# U-blox_ZED_F9P_GPS_RTK.net
KiCad netlist of a schematic drawn in EasyEDA Pro
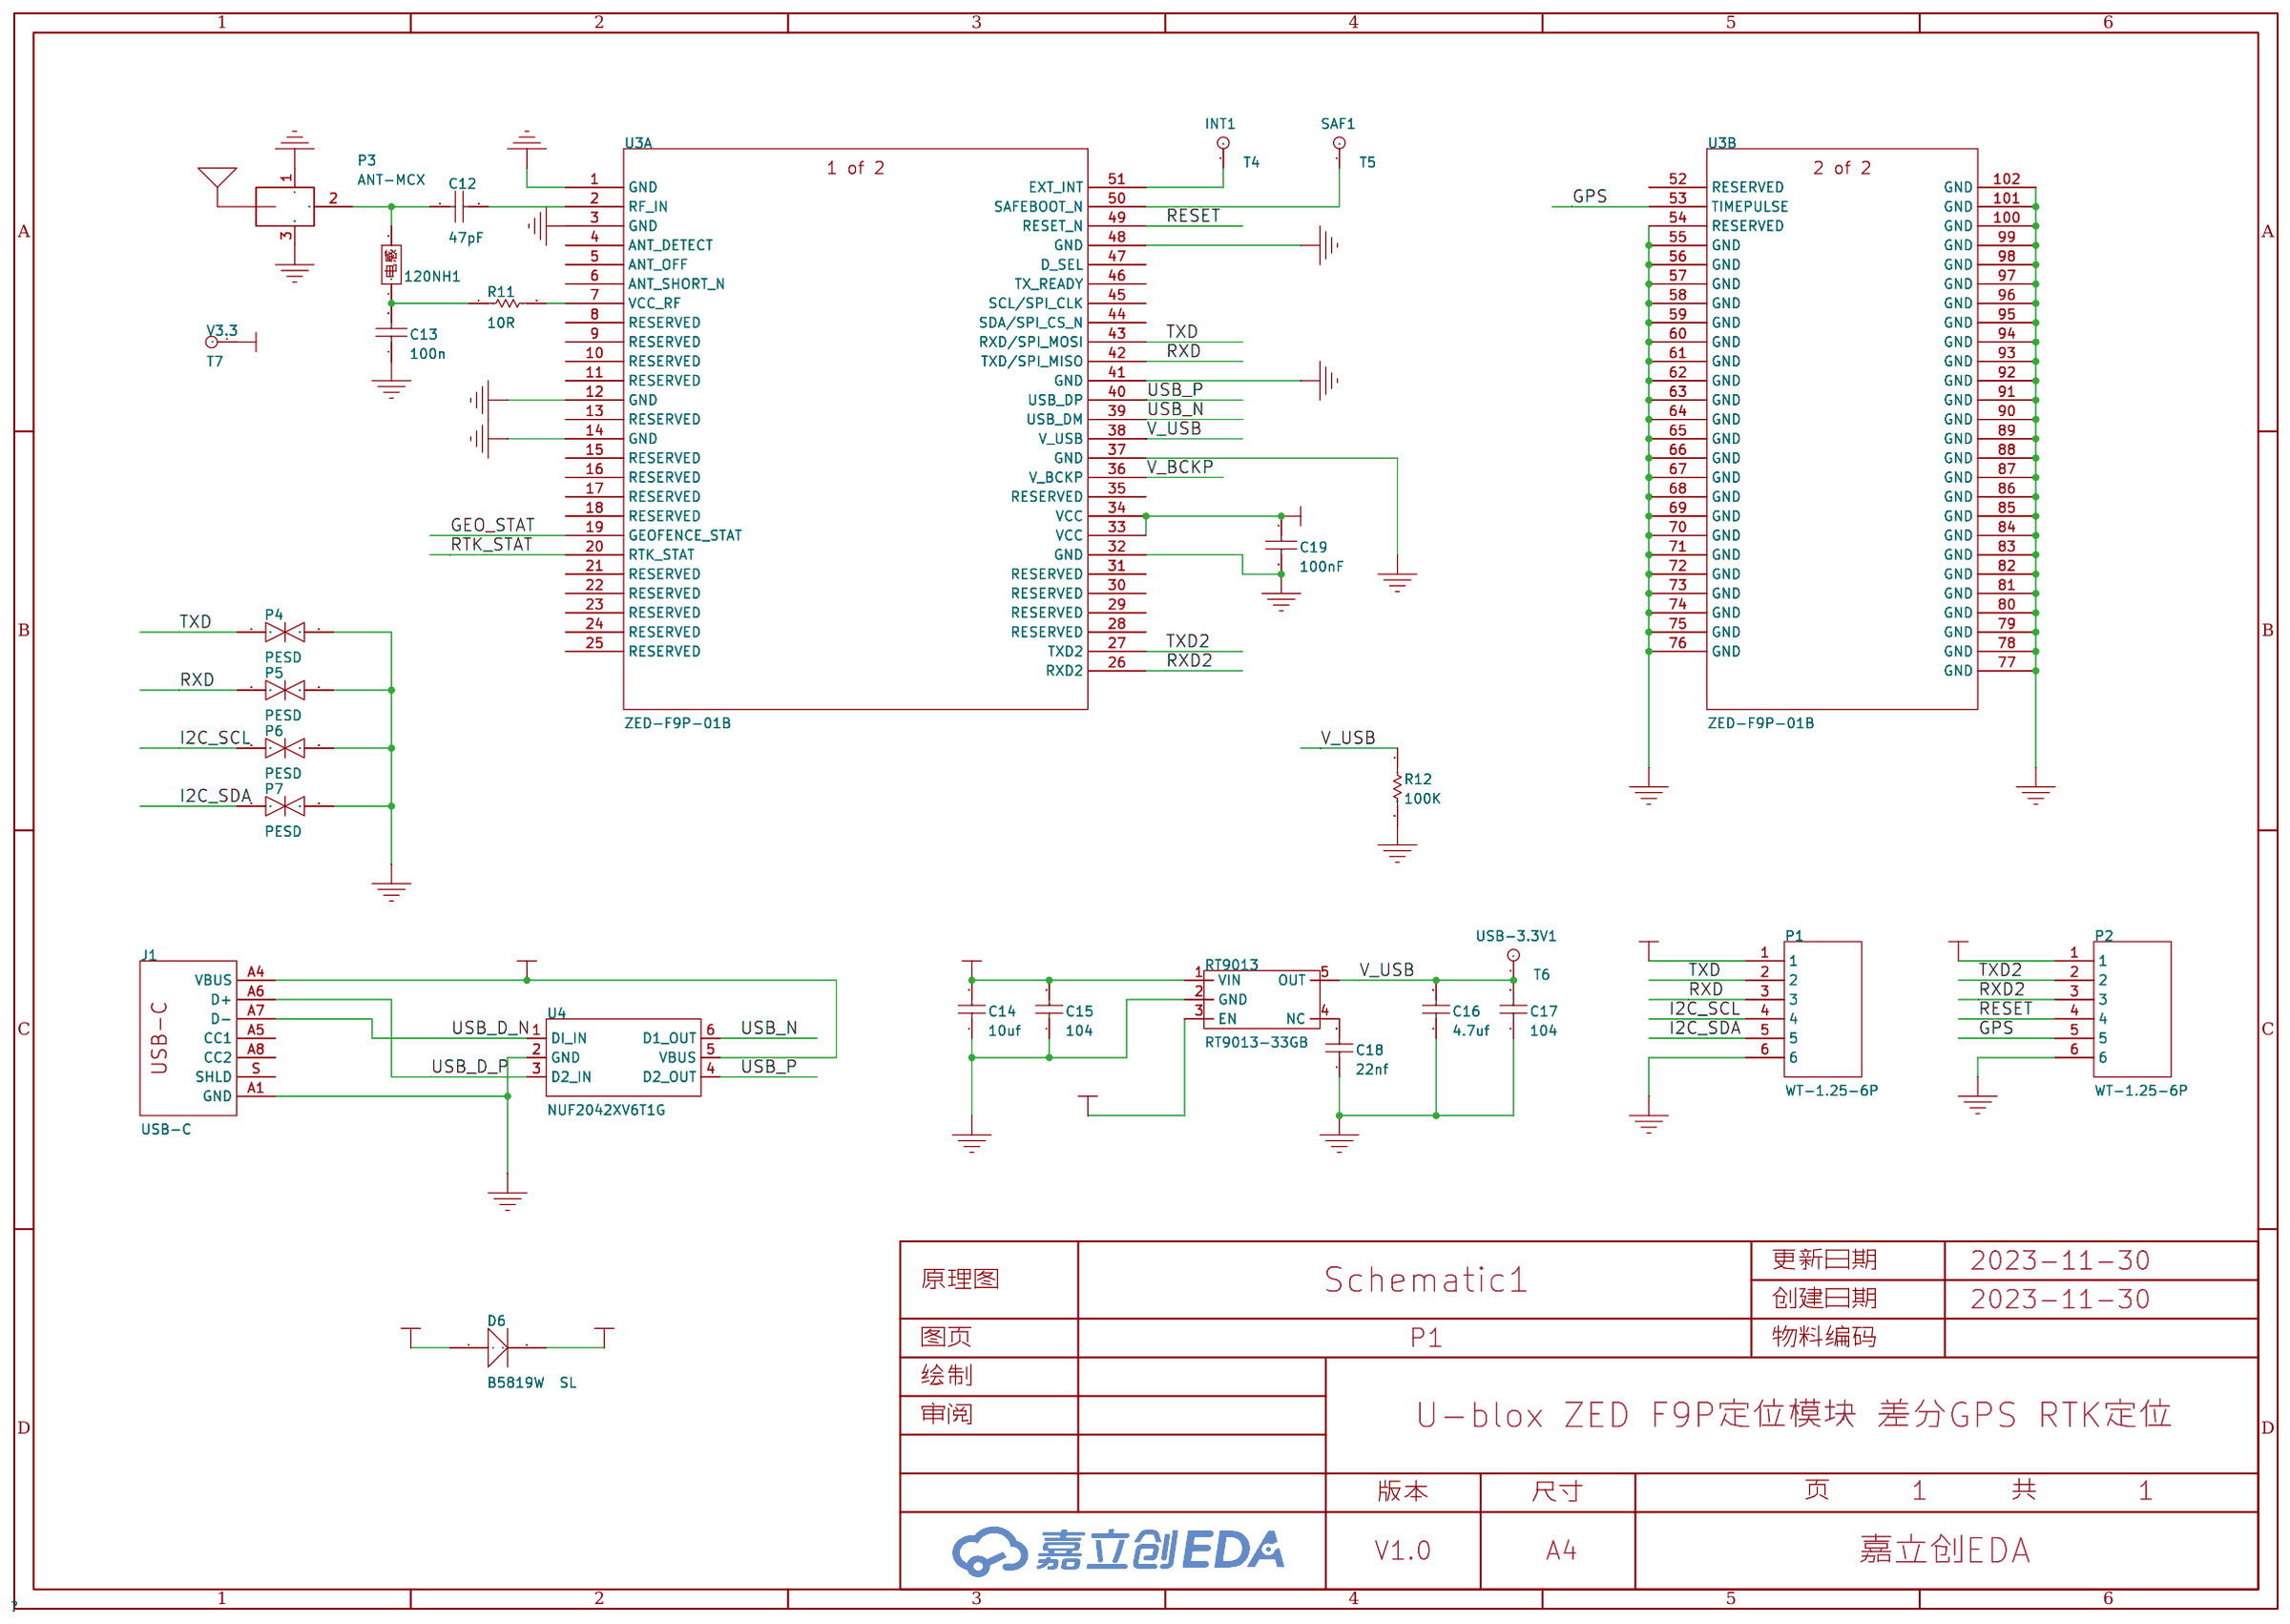
[diagram p0: P1_GPS_F9P]
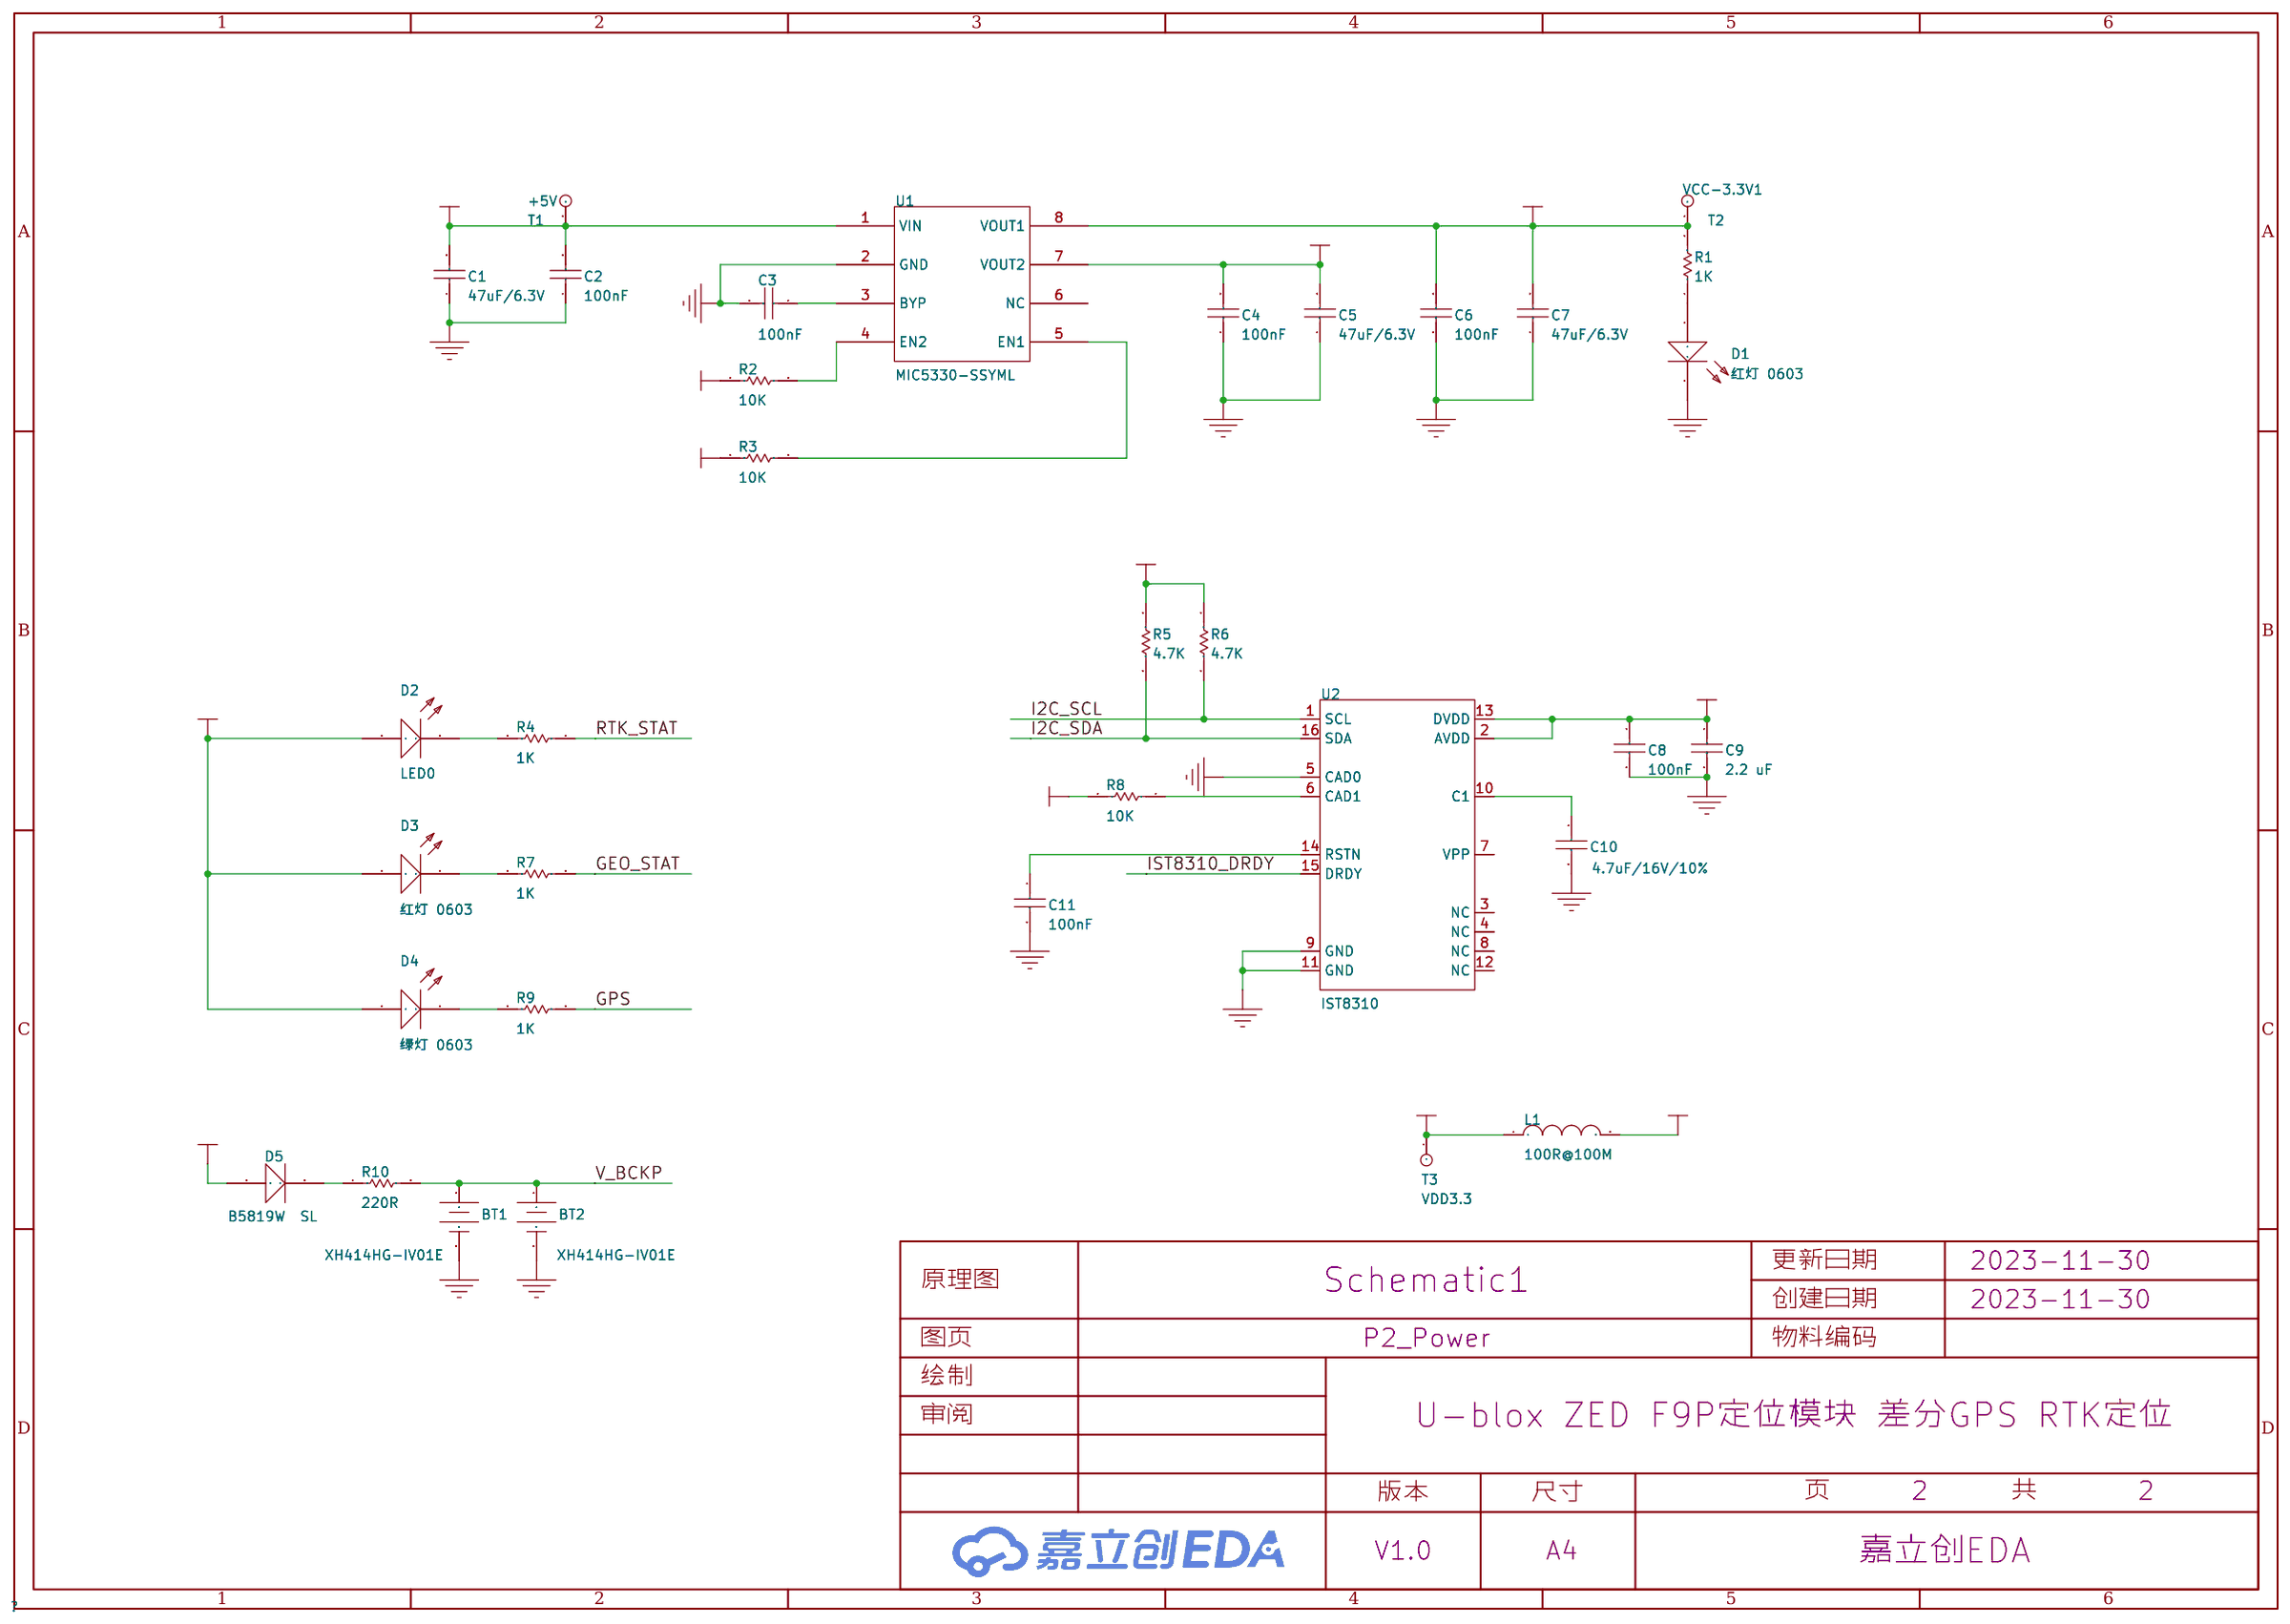
[diagram p1: P2_Power]

(export (version "E")
  (design (tool "Eeschema 10.0.6"))
  (components
    (comp (ref "120NH1") (value "L") (footprint "easyedapro:0402R") (libsource (lib "easyedapro") (part "L")))
    (comp (ref "C12")
      (value "100pF")
      (footprint "easyedapro:0603C")
      (description "Capacitor")
      (fields (field (name "Publisher") "Altium Limited"))
      (libsource (lib "easyedapro") (part "Cap"))
    )
    (comp (ref "C13")
      (value "100pF")
      (footprint "easyedapro:0603C")
      (description "Capacitor")
      (fields (field (name "Publisher") "Altium Limited"))
      (libsource (lib "easyedapro") (part "Cap"))
    )
    (comp (ref "C14")
      (value "10uf")
      (footprint "easyedapro:0603C")
      (description "无极性电容")
      (libsource (lib "easyedapro") (part "CAP"))
    )
    (comp (ref "C15")
      (value "104")
      (footprint "easyedapro:0603C")
      (description "无极性电容")
      (libsource (lib "easyedapro") (part "CAP"))
    )
    (comp (ref "C16")
      (value "4.7uf")
      (footprint "easyedapro:0603C")
      (description "无极性电容")
      (libsource (lib "easyedapro") (part "CAP"))
    )
    (comp (ref "C17")
      (value "104")
      (footprint "easyedapro:0603C")
      (description "无极性电容")
      (libsource (lib "easyedapro") (part "CAP"))
    )
    (comp (ref "C18")
      (value "22nf")
      (footprint "easyedapro:0603C")
      (description "无极性电容")
      (libsource (lib "easyedapro") (part "CAP"))
    )
    (comp (ref "C19")
      (value "100pF")
      (footprint "easyedapro:0603C")
      (description "Capacitor")
      (fields (field (name "Publisher") "Altium Limited"))
      (libsource (lib "easyedapro") (part "Cap"))
    )
    (comp (ref "D6")
      (value "B5819W  SL")
      (footprint "easyedapro:SOD-123")
      (description "肖特基二极管")
      (libsource (lib "easyedapro") (part "SOD-123 B5819W  SL"))
    )
    (comp (ref "INT1") (value "T4") (footprint "easyedapro:TP") (libsource (lib "easyedapro") (part "TP")))
    (comp (ref "J1")
      (value "USB-C")
      (footprint "easyedapro:USB-Type-C")
      (libsource (lib "easyedapro") (part "USB3.1"))
    )
    (comp (ref "P1")
      (value "WT-1.25-6P")
      (footprint "easyedapro:GH-1.25-6P")
      (libsource (lib "easyedapro") (part "GH-1.25-6P"))
    )
    (comp (ref "P2")
      (value "WT-1.25-6P")
      (footprint "easyedapro:GH-1.25-6P")
      (libsource (lib "easyedapro") (part "GH-1.25-6P"))
    )
    (comp (ref "P3")
      (value "ANT-MCX")
      (footprint "easyedapro:ANT-MCX")
      (libsource (lib "easyedapro") (part "ANT"))
    )
    (comp (ref "P4")
      (value "PESD")
      (footprint "easyedapro:PESD0402")
      (description "PESD 0402")
      (libsource (lib "easyedapro") (part "PESD"))
    )
    (comp (ref "P5")
      (value "PESD")
      (footprint "easyedapro:PESD0402")
      (description "PESD 0402")
      (libsource (lib "easyedapro") (part "PESD"))
    )
    (comp (ref "P6")
      (value "PESD")
      (footprint "easyedapro:PESD0402")
      (description "PESD 0402")
      (libsource (lib "easyedapro") (part "PESD"))
    )
    (comp (ref "P7")
      (value "PESD")
      (footprint "easyedapro:PESD0402")
      (description "PESD 0402")
      (libsource (lib "easyedapro") (part "PESD"))
    )
    (comp (ref "R11")
      (value "1K")
      (footprint "easyedapro:0402R")
      (description "Resistor")
      (fields (field (name "Publisher") "Altium Limited"))
      (libsource (lib "easyedapro") (part "Res1"))
    )
    (comp (ref "R12")
      (value "1K")
      (footprint "easyedapro:0402R")
      (description "Resistor")
      (fields (field (name "Publisher") "Altium Limited"))
      (libsource (lib "easyedapro") (part "Res1"))
    )
    (comp (ref "RT9013")
      (value "RT9013-33GB")
      (footprint "easyedapro:SOT23-5L")
      (description "3.3V 500mA LDO")
      (libsource (lib "easyedapro") (part "RT9013"))
    )
    (comp (ref "SAF1") (value "T5") (footprint "easyedapro:TP") (libsource (lib "easyedapro") (part "TP")))
    (comp (ref "U3")
      (value "ZED-F9P-01B")
      (footprint "easyedapro:ZED-F9P-01B_UBL")
      (description "多频 GNSS 接收机")
      (fields
        (field (name "Manufacturer_Part_Number") "ZED-F9R-01B")
        (field (name "Copyright") "Copyright (C) 2022 Ultra Librarian. All rights reserved.")
      )
      (libsource (lib "easyedapro") (part "ZED-F9P-01B"))
    )
    (comp (ref "U4")
      (value "NUF2042XV6T1G")
      (footprint "easyedapro:SOT-563-6")
      (libsource (lib "easyedapro") (part "NUF2042XV6T1G"))
    )
    (comp (ref "USB-3.3V1")
      (value "T6")
      (footprint "easyedapro:TP")
      (libsource (lib "easyedapro") (part "TP"))
    )
    (comp (ref "V3.3") (value "T7") (footprint "easyedapro:TP") (libsource (lib "easyedapro") (part "TP")))
    (comp (ref "BT1")
      (value "XH414HG-IV01E")
      (footprint "easyedapro:XH414HG-IV01E")
      (libsource (lib "easyedapro") (part "Battery"))
    )
    (comp (ref "BT2")
      (value "XH414HG-IV01E")
      (footprint "easyedapro:XH414HG-IV01E")
      (libsource (lib "easyedapro") (part "Battery"))
    )
    (comp (ref "C1")
      (value "100pF")
      (footprint "easyedapro:0603C")
      (description "Capacitor")
      (fields (field (name "Publisher") "Altium Limited"))
      (libsource (lib "easyedapro") (part "Cap"))
    )
    (comp (ref "C2")
      (value "100pF")
      (footprint "easyedapro:0603C")
      (description "Capacitor")
      (fields (field (name "Publisher") "Altium Limited"))
      (libsource (lib "easyedapro") (part "Cap"))
    )
    (comp (ref "C3")
      (value "100pF")
      (footprint "easyedapro:0603C")
      (description "Capacitor")
      (fields (field (name "Publisher") "Altium Limited"))
      (libsource (lib "easyedapro") (part "Cap"))
    )
    (comp (ref "C4")
      (value "100pF")
      (footprint "easyedapro:0603C")
      (description "Capacitor")
      (fields (field (name "Publisher") "Altium Limited"))
      (libsource (lib "easyedapro") (part "Cap"))
    )
    (comp (ref "C5")
      (value "100pF")
      (footprint "easyedapro:0603C")
      (description "Capacitor")
      (fields (field (name "Publisher") "Altium Limited"))
      (libsource (lib "easyedapro") (part "Cap"))
    )
    (comp (ref "C6")
      (value "100pF")
      (footprint "easyedapro:0603C")
      (description "Capacitor")
      (fields (field (name "Publisher") "Altium Limited"))
      (libsource (lib "easyedapro") (part "Cap"))
    )
    (comp (ref "C7")
      (value "100pF")
      (footprint "easyedapro:0603C")
      (description "Capacitor")
      (fields (field (name "Publisher") "Altium Limited"))
      (libsource (lib "easyedapro") (part "Cap"))
    )
    (comp (ref "C8")
      (value "100pF")
      (footprint "easyedapro:0603C")
      (description "Capacitor")
      (fields (field (name "Publisher") "Altium Limited"))
      (libsource (lib "easyedapro") (part "Cap"))
    )
    (comp (ref "C9")
      (value "100pF")
      (footprint "easyedapro:0603C")
      (description "Capacitor")
      (fields (field (name "Publisher") "Altium Limited"))
      (libsource (lib "easyedapro") (part "Cap"))
    )
    (comp (ref "C10")
      (value "100pF")
      (footprint "easyedapro:0603C")
      (description "Capacitor")
      (fields (field (name "Publisher") "Altium Limited"))
      (libsource (lib "easyedapro") (part "Cap"))
    )
    (comp (ref "C11")
      (value "100pF")
      (footprint "easyedapro:0603C")
      (description "Capacitor")
      (fields (field (name "Publisher") "Altium Limited"))
      (libsource (lib "easyedapro") (part "Cap"))
    )
    (comp (ref "D1")
      (value "红灯 0603")
      (footprint "easyedapro:0603_LED_S1")
      (description "发光二极管")
      (libsource (lib "easyedapro") (part "0603 红灯"))
    )
    (comp (ref "D2")
      (value "LED0")
      (footprint "easyedapro:0603D")
      (description "Typical INFRARED GaAs LED")
      (fields (field (name "Publisher") "Altium Limited"))
      (libsource (lib "easyedapro") (part "LED0"))
    )
    (comp (ref "D3")
      (value "红灯 0603")
      (footprint "easyedapro:0603_LED_S1")
      (description "发光二极管")
      (libsource (lib "easyedapro") (part "0603 红灯"))
    )
    (comp (ref "D4")
      (value "绿灯 0603")
      (footprint "easyedapro:0603_LED_S1")
      (description "发光二极管")
      (libsource (lib "easyedapro") (part "0603 绿灯"))
    )
    (comp (ref "D5")
      (value "B5819W  SL")
      (footprint "easyedapro:SOD-123")
      (description "肖特基二极管")
      (libsource (lib "easyedapro") (part "SOD-123 B5819W  SL"))
    )
    (comp (ref "L1")
      (value "10mH")
      (footprint "easyedapro:0603L")
      (description "Inductor")
      (fields (field (name "Publisher") "Altium Limited"))
      (libsource (lib "easyedapro") (part "Inductor"))
    )
    (comp (ref "R1")
      (value "1K")
      (footprint "easyedapro:0402R")
      (description "Resistor")
      (fields (field (name "Publisher") "Altium Limited"))
      (libsource (lib "easyedapro") (part "Res1"))
    )
    (comp (ref "R2")
      (value "1K")
      (footprint "easyedapro:0402R")
      (description "Resistor")
      (fields (field (name "Publisher") "Altium Limited"))
      (libsource (lib "easyedapro") (part "Res1"))
    )
    (comp (ref "R3")
      (value "1K")
      (footprint "easyedapro:0402R")
      (description "Resistor")
      (fields (field (name "Publisher") "Altium Limited"))
      (libsource (lib "easyedapro") (part "Res1"))
    )
    (comp (ref "R4")
      (value "1K")
      (footprint "easyedapro:0402R")
      (description "Resistor")
      (fields (field (name "Publisher") "Altium Limited"))
      (libsource (lib "easyedapro") (part "Res1"))
    )
    (comp (ref "R5")
      (value "1K")
      (footprint "easyedapro:0402R")
      (description "Resistor")
      (fields (field (name "Publisher") "Altium Limited"))
      (libsource (lib "easyedapro") (part "Res1"))
    )
    (comp (ref "R6")
      (value "1K")
      (footprint "easyedapro:0402R")
      (description "Resistor")
      (fields (field (name "Publisher") "Altium Limited"))
      (libsource (lib "easyedapro") (part "Res1"))
    )
    (comp (ref "R7")
      (value "1K")
      (footprint "easyedapro:0402R")
      (description "Resistor")
      (fields (field (name "Publisher") "Altium Limited"))
      (libsource (lib "easyedapro") (part "Res1"))
    )
    (comp (ref "R8")
      (value "1K")
      (footprint "easyedapro:0402R")
      (description "Resistor")
      (fields (field (name "Publisher") "Altium Limited"))
      (libsource (lib "easyedapro") (part "Res1"))
    )
    (comp (ref "R9")
      (value "1K")
      (footprint "easyedapro:0402R")
      (description "Resistor")
      (fields (field (name "Publisher") "Altium Limited"))
      (libsource (lib "easyedapro") (part "Res1"))
    )
    (comp (ref "R10")
      (value "1K")
      (footprint "easyedapro:0402R")
      (description "Resistor")
      (fields (field (name "Publisher") "Altium Limited"))
      (libsource (lib "easyedapro") (part "Res1"))
    )
    (comp (ref "T1") (value "+5V") (footprint "easyedapro:TP") (libsource (lib "easyedapro") (part "TP")))
    (comp (ref "T3") (value "VDD3.3") (footprint "easyedapro:TP") (libsource (lib "easyedapro") (part "TP")))
    (comp (ref "U1")
      (value "MIC5330-SSYML")
      (footprint "easyedapro:MIC5330-SSYML-TR")
      (libsource (lib "easyedapro") (part "MIC5330-SSYML"))
    )
    (comp (ref "U2")
      (value "IST8310")
      (footprint "easyedapro:LGA16-ITS8310")
      (libsource (lib "easyedapro") (part "IST8310"))
    )
    (comp (ref "VCC-3.3V1")
      (value "T2")
      (footprint "easyedapro:TP")
      (libsource (lib "easyedapro") (part "TP"))
    )
  )
  (nets
    (net (code "1") (name "GEO_STAT") (class "Default")
      (node (ref "R7") (pin "2") (pinfunction "2_2") (pintype "unspecified"))
      (node (ref "U3") (pin "19") (pinfunction "GEOFENCE_STAT_19") (pintype "output"))
    )
    (net (code "2") (name "GND") (class "Default")
      (node (ref "BT1") (pin "2") (pinfunction "2_2") (pintype "unspecified"))
      (node (ref "BT2") (pin "2") (pinfunction "2_2") (pintype "unspecified"))
      (node (ref "C1") (pin "1") (pinfunction "1_1") (pintype "unspecified"))
      (node (ref "C10") (pin "2") (pinfunction "2_2") (pintype "unspecified"))
      (node (ref "C11") (pin "2") (pinfunction "2_2") (pintype "unspecified"))
      (node (ref "C13") (pin "1") (pinfunction "1_1") (pintype "unspecified"))
      (node (ref "C14") (pin "1") (pinfunction "1_1") (pintype "unspecified"))
      (node (ref "C15") (pin "1") (pinfunction "1_1") (pintype "unspecified"))
      (node (ref "C16") (pin "1") (pinfunction "1_1") (pintype "unspecified"))
      (node (ref "C17") (pin "1") (pinfunction "1_1") (pintype "unspecified"))
      (node (ref "C18") (pin "1") (pinfunction "1_1") (pintype "unspecified"))
      (node (ref "C19") (pin "2") (pinfunction "2_2") (pintype "unspecified"))
      (node (ref "C2") (pin "1") (pinfunction "1_1") (pintype "unspecified"))
      (node (ref "C3") (pin "2") (pinfunction "2_2") (pintype "unspecified"))
      (node (ref "C4") (pin "1") (pinfunction "1_1") (pintype "unspecified"))
      (node (ref "C5") (pin "1") (pinfunction "1_1") (pintype "unspecified"))
      (node (ref "C6") (pin "1") (pinfunction "1_1") (pintype "unspecified"))
      (node (ref "C7") (pin "1") (pinfunction "1_1") (pintype "unspecified"))
      (node (ref "C8") (pin "2") (pinfunction "2_2") (pintype "unspecified"))
      (node (ref "C9") (pin "2") (pinfunction "2_2") (pintype "unspecified"))
      (node (ref "D1") (pin "K") (pinfunction "K_K") (pintype "unspecified"))
      (node (ref "J1") (pin "A1") (pinfunction "GND_A1") (pintype "unspecified"))
      (node (ref "P1") (pin "6") (pinfunction "6_6") (pintype "unspecified"))
      (node (ref "P2") (pin "6") (pinfunction "6_6") (pintype "unspecified"))
      (node (ref "P3") (pin "1") (pinfunction "1_1") (pintype "unspecified"))
      (node (ref "P3") (pin "3") (pinfunction "3_3") (pintype "unspecified"))
      (node (ref "P4") (pin "2") (pinfunction "2_2") (pintype "unspecified"))
      (node (ref "P5") (pin "2") (pinfunction "2_2") (pintype "unspecified"))
      (node (ref "P6") (pin "2") (pinfunction "2_2") (pintype "unspecified"))
      (node (ref "P7") (pin "2") (pinfunction "2_2") (pintype "unspecified"))
      (node (ref "R12") (pin "2") (pinfunction "2_2") (pintype "unspecified"))
      (node (ref "RT9013") (pin "2") (pinfunction "GND_2") (pintype "unspecified"))
      (node (ref "U1") (pin "2") (pinfunction "GND_2") (pintype "unspecified"))
      (node (ref "U2") (pin "11") (pinfunction "GND_11") (pintype "unspecified"))
      (node (ref "U2") (pin "5") (pinfunction "CAD0_5") (pintype "unspecified"))
      (node (ref "U2") (pin "9") (pinfunction "GND_9") (pintype "unspecified"))
      (node (ref "U3") (pin "1") (pinfunction "GND_1") (pintype "unspecified"))
      (node (ref "U3") (pin "100") (pinfunction "GND_100") (pintype "unspecified"))
      (node (ref "U3") (pin "101") (pinfunction "GND_101") (pintype "unspecified"))
      (node (ref "U3") (pin "102") (pinfunction "GND_102") (pintype "unspecified"))
      (node (ref "U3") (pin "12") (pinfunction "GND_12") (pintype "unspecified"))
      (node (ref "U3") (pin "14") (pinfunction "GND_14") (pintype "unspecified"))
      (node (ref "U3") (pin "3") (pinfunction "GND_3") (pintype "unspecified"))
      (node (ref "U3") (pin "32") (pinfunction "GND_32") (pintype "unspecified"))
      (node (ref "U3") (pin "37") (pinfunction "GND_37") (pintype "unspecified"))
      (node (ref "U3") (pin "41") (pinfunction "GND_41") (pintype "unspecified"))
      (node (ref "U3") (pin "48") (pinfunction "GND_48") (pintype "unspecified"))
      (node (ref "U3") (pin "54") (pinfunction "RESERVED_54") (pintype "unspecified"))
      (node (ref "U3") (pin "55") (pinfunction "GND_55") (pintype "unspecified"))
      (node (ref "U3") (pin "56") (pinfunction "GND_56") (pintype "unspecified"))
      (node (ref "U3") (pin "57") (pinfunction "GND_57") (pintype "unspecified"))
      (node (ref "U3") (pin "58") (pinfunction "GND_58") (pintype "unspecified"))
      (node (ref "U3") (pin "59") (pinfunction "GND_59") (pintype "unspecified"))
      (node (ref "U3") (pin "60") (pinfunction "GND_60") (pintype "unspecified"))
      (node (ref "U3") (pin "61") (pinfunction "GND_61") (pintype "unspecified"))
      (node (ref "U3") (pin "62") (pinfunction "GND_62") (pintype "unspecified"))
      (node (ref "U3") (pin "63") (pinfunction "GND_63") (pintype "unspecified"))
      (node (ref "U3") (pin "64") (pinfunction "GND_64") (pintype "unspecified"))
      (node (ref "U3") (pin "65") (pinfunction "GND_65") (pintype "unspecified"))
      (node (ref "U3") (pin "66") (pinfunction "GND_66") (pintype "unspecified"))
      (node (ref "U3") (pin "67") (pinfunction "GND_67") (pintype "unspecified"))
      (node (ref "U3") (pin "68") (pinfunction "GND_68") (pintype "unspecified"))
      (node (ref "U3") (pin "69") (pinfunction "GND_69") (pintype "unspecified"))
      (node (ref "U3") (pin "70") (pinfunction "GND_70") (pintype "unspecified"))
      (node (ref "U3") (pin "71") (pinfunction "GND_71") (pintype "unspecified"))
      (node (ref "U3") (pin "72") (pinfunction "GND_72") (pintype "unspecified"))
      (node (ref "U3") (pin "73") (pinfunction "GND_73") (pintype "unspecified"))
      (node (ref "U3") (pin "74") (pinfunction "GND_74") (pintype "unspecified"))
      (node (ref "U3") (pin "75") (pinfunction "GND_75") (pintype "unspecified"))
      (node (ref "U3") (pin "76") (pinfunction "GND_76") (pintype "unspecified"))
      (node (ref "U3") (pin "77") (pinfunction "GND_77") (pintype "unspecified"))
      (node (ref "U3") (pin "78") (pinfunction "GND_78") (pintype "unspecified"))
      (node (ref "U3") (pin "79") (pinfunction "GND_79") (pintype "unspecified"))
      (node (ref "U3") (pin "80") (pinfunction "GND_80") (pintype "unspecified"))
      (node (ref "U3") (pin "81") (pinfunction "GND_81") (pintype "unspecified"))
      (node (ref "U3") (pin "82") (pinfunction "GND_82") (pintype "unspecified"))
      (node (ref "U3") (pin "83") (pinfunction "GND_83") (pintype "unspecified"))
      (node (ref "U3") (pin "84") (pinfunction "GND_84") (pintype "unspecified"))
      (node (ref "U3") (pin "85") (pinfunction "GND_85") (pintype "unspecified"))
      (node (ref "U3") (pin "86") (pinfunction "GND_86") (pintype "unspecified"))
      (node (ref "U3") (pin "87") (pinfunction "GND_87") (pintype "unspecified"))
      (node (ref "U3") (pin "88") (pinfunction "GND_88") (pintype "unspecified"))
      (node (ref "U3") (pin "89") (pinfunction "GND_89") (pintype "unspecified"))
      (node (ref "U3") (pin "90") (pinfunction "GND_90") (pintype "unspecified"))
      (node (ref "U3") (pin "91") (pinfunction "GND_91") (pintype "unspecified"))
      (node (ref "U3") (pin "92") (pinfunction "GND_92") (pintype "unspecified"))
      (node (ref "U3") (pin "93") (pinfunction "GND_93") (pintype "unspecified"))
      (node (ref "U3") (pin "94") (pinfunction "GND_94") (pintype "unspecified"))
      (node (ref "U3") (pin "95") (pinfunction "GND_95") (pintype "unspecified"))
      (node (ref "U3") (pin "96") (pinfunction "GND_96") (pintype "unspecified"))
      (node (ref "U3") (pin "97") (pinfunction "GND_97") (pintype "unspecified"))
      (node (ref "U3") (pin "98") (pinfunction "GND_98") (pintype "unspecified"))
      (node (ref "U3") (pin "99") (pinfunction "GND_99") (pintype "unspecified"))
      (node (ref "U4") (pin "2") (pinfunction "GND_2") (pintype "unspecified"))
    )
    (net (code "3") (name "GPS") (class "Default")
      (node (ref "P2") (pin "5") (pinfunction "5_5") (pintype "unspecified"))
      (node (ref "R9") (pin "2") (pinfunction "2_2") (pintype "unspecified"))
      (node (ref "U3") (pin "53") (pinfunction "TIMEPULSE_53") (pintype "output"))
    )
    (net (code "4") (name "I2C_SCL") (class "Default")
      (node (ref "P1") (pin "4") (pinfunction "4_4") (pintype "unspecified"))
      (node (ref "P6") (pin "1") (pinfunction "1_1") (pintype "unspecified"))
      (node (ref "R6") (pin "2") (pinfunction "2_2") (pintype "unspecified"))
      (node (ref "U2") (pin "1") (pinfunction "SCL_1") (pintype "unspecified"))
    )
    (net (code "5") (name "I2C_SDA") (class "Default")
      (node (ref "P1") (pin "5") (pinfunction "5_5") (pintype "unspecified"))
      (node (ref "P7") (pin "1") (pinfunction "1_1") (pintype "unspecified"))
      (node (ref "R5") (pin "2") (pinfunction "2_2") (pintype "unspecified"))
      (node (ref "U2") (pin "16") (pinfunction "SDA_16") (pintype "unspecified"))
    )
    (net (code "6") (name "IST8310_DRDY") (class "Default")
      (node (ref "U2") (pin "15") (pinfunction "DRDY_15") (pintype "unspecified"))
    )
    (net (code "7") (name "Net-(120NH1-Pad1)") (class "Default")
      (node (ref "120NH1") (pin "1") (pinfunction "1_1") (pintype "unspecified"))
      (node (ref "C13") (pin "2") (pinfunction "2_2") (pintype "unspecified"))
      (node (ref "R11") (pin "1") (pinfunction "1_1") (pintype "unspecified"))
    )
    (net (code "8") (name "Net-(120NH1-Pad2)") (class "Default")
      (node (ref "120NH1") (pin "2") (pinfunction "2_2") (pintype "unspecified"))
      (node (ref "C12") (pin "1") (pinfunction "1_1") (pintype "unspecified"))
      (node (ref "P3") (pin "2") (pinfunction "2_2") (pintype "unspecified"))
    )
    (net (code "9") (name "Net-(D1-PadA)") (class "Default")
      (node (ref "D1") (pin "A") (pinfunction "A_A") (pintype "unspecified"))
      (node (ref "R1") (pin "1") (pinfunction "1_1") (pintype "unspecified"))
    )
    (net (code "10") (name "Net-(D2-K)") (class "Default")
      (node (ref "D2") (pin "2") (pinfunction "K_2") (pintype "unspecified"))
      (node (ref "R4") (pin "2") (pinfunction "2_2") (pintype "unspecified"))
    )
    (net (code "11") (name "Net-(D3-PadK)") (class "Default")
      (node (ref "D3") (pin "K") (pinfunction "K_K") (pintype "unspecified"))
      (node (ref "R7") (pin "1") (pinfunction "1_1") (pintype "unspecified"))
    )
    (net (code "12") (name "Net-(D4-PadK)") (class "Default")
      (node (ref "D4") (pin "K") (pinfunction "K_K") (pintype "unspecified"))
      (node (ref "R9") (pin "1") (pinfunction "1_1") (pintype "unspecified"))
    )
    (net (code "13") (name "Net-(D5-K)") (class "Default")
      (node (ref "D5") (pin "2") (pinfunction "K_2") (pintype "unspecified"))
      (node (ref "R10") (pin "1") (pinfunction "1_1") (pintype "unspecified"))
    )
    (net (code "14") (name "Net-(RT9013-NC)") (class "Default")
      (node (ref "C18") (pin "2") (pinfunction "2_2") (pintype "unspecified"))
      (node (ref "RT9013") (pin "4") (pinfunction "NC_4") (pintype "unspecified"))
    )
    (net (code "15") (name "Net-(U1-BYP)") (class "Default")
      (node (ref "C3") (pin "1") (pinfunction "1_1") (pintype "unspecified"))
      (node (ref "U1") (pin "3") (pinfunction "BYP_3") (pintype "unspecified"))
    )
    (net (code "16") (name "Net-(U1-EN1)") (class "Default")
      (node (ref "R3") (pin "2") (pinfunction "2_2") (pintype "unspecified"))
      (node (ref "U1") (pin "5") (pinfunction "EN1_5") (pintype "unspecified"))
    )
    (net (code "17") (name "Net-(U1-EN2)") (class "Default")
      (node (ref "R2") (pin "2") (pinfunction "2_2") (pintype "unspecified"))
      (node (ref "U1") (pin "4") (pinfunction "EN2_4") (pintype "unspecified"))
    )
    (net (code "18") (name "Net-(U2-C1)") (class "Default")
      (node (ref "C10") (pin "1") (pinfunction "1_1") (pintype "unspecified"))
      (node (ref "U2") (pin "10") (pinfunction "C1_10") (pintype "unspecified"))
    )
    (net (code "19") (name "Net-(U2-CAD1)") (class "Default")
      (node (ref "R8") (pin "1") (pinfunction "1_1") (pintype "unspecified"))
      (node (ref "U2") (pin "6") (pinfunction "CAD1_6") (pintype "unspecified"))
    )
    (net (code "20") (name "Net-(U2-RSTN)") (class "Default")
      (node (ref "C11") (pin "1") (pinfunction "1_1") (pintype "unspecified"))
      (node (ref "U2") (pin "14") (pinfunction "RSTN_14") (pintype "unspecified"))
    )
    (net (code "21") (name "Net-(U3A-EXT_INT)") (class "Default")
      (node (ref "INT1") (pin "1") (pinfunction "1_1") (pintype "unspecified"))
      (node (ref "U3") (pin "51") (pinfunction "EXT_INT_51") (pintype "input"))
    )
    (net (code "22") (name "Net-(U3A-RF_IN)") (class "Default")
      (node (ref "C12") (pin "2") (pinfunction "2_2") (pintype "unspecified"))
      (node (ref "U3") (pin "2") (pinfunction "RF_IN_2") (pintype "input"))
    )
    (net (code "23") (name "Net-(U3A-SAFEBOOT_N)") (class "Default")
      (node (ref "SAF1") (pin "1") (pinfunction "1_1") (pintype "unspecified"))
      (node (ref "U3") (pin "50") (pinfunction "SAFEBOOT_N_50") (pintype "input"))
    )
    (net (code "24") (name "Net-(U3A-VCC_RF)") (class "Default")
      (node (ref "R11") (pin "2") (pinfunction "2_2") (pintype "unspecified"))
      (node (ref "U3") (pin "7") (pinfunction "VCC_RF_7") (pintype "unspecified"))
    )
    (net (code "25") (name "RESET") (class "Default")
      (node (ref "P2") (pin "4") (pinfunction "4_4") (pintype "unspecified"))
      (node (ref "U3") (pin "49") (pinfunction "RESET_N_49") (pintype "input"))
    )
    (net (code "26") (name "RTK_STAT") (class "Default")
      (node (ref "R4") (pin "1") (pinfunction "1_1") (pintype "unspecified"))
      (node (ref "U3") (pin "20") (pinfunction "RTK_STAT_20") (pintype "output"))
    )
    (net (code "27") (name "RXD") (class "Default")
      (node (ref "P1") (pin "3") (pinfunction "3_3") (pintype "unspecified"))
      (node (ref "P5") (pin "1") (pinfunction "1_1") (pintype "unspecified"))
      (node (ref "U3") (pin "42") (pinfunction "TXD/SPI_MISO_42") (pintype "output"))
    )
    (net (code "28") (name "RXD2") (class "Default")
      (node (ref "P2") (pin "3") (pinfunction "3_3") (pintype "unspecified"))
      (node (ref "U3") (pin "26") (pinfunction "RXD2_26") (pintype "input"))
    )
    (net (code "29") (name "SEN_3V3") (class "Default")
      (node (ref "C8") (pin "1") (pinfunction "1_1") (pintype "unspecified"))
      (node (ref "C9") (pin "1") (pinfunction "1_1") (pintype "unspecified"))
      (node (ref "L1") (pin "2") (pinfunction "2_2") (pintype "unspecified"))
      (node (ref "R5") (pin "1") (pinfunction "1_1") (pintype "unspecified"))
      (node (ref "R6") (pin "1") (pinfunction "1_1") (pintype "unspecified"))
      (node (ref "R8") (pin "2") (pinfunction "2_2") (pintype "unspecified"))
      (node (ref "U2") (pin "13") (pinfunction "DVDD_13") (pintype "unspecified"))
      (node (ref "U2") (pin "2") (pinfunction "AVDD_2") (pintype "unspecified"))
    )
    (net (code "30") (name "TXD") (class "Default")
      (node (ref "P1") (pin "2") (pinfunction "2_2") (pintype "unspecified"))
      (node (ref "P4") (pin "1") (pinfunction "1_1") (pintype "unspecified"))
      (node (ref "U3") (pin "43") (pinfunction "RXD/SPI_MOSI_43") (pintype "input"))
    )
    (net (code "31") (name "TXD2") (class "Default")
      (node (ref "P2") (pin "2") (pinfunction "2_2") (pintype "unspecified"))
      (node (ref "U3") (pin "27") (pinfunction "TXD2_27") (pintype "output"))
    )
    (net (code "32") (name "USB_D_N") (class "Default")
      (node (ref "J1") (pin "A7") (pinfunction "D-_A7") (pintype "unspecified"))
      (node (ref "U4") (pin "1") (pinfunction "DI_IN_1") (pintype "unspecified"))
    )
    (net (code "33") (name "USB_D_P") (class "Default")
      (node (ref "J1") (pin "A6") (pinfunction "D+_A6") (pintype "unspecified"))
      (node (ref "U4") (pin "3") (pinfunction "D2_IN_3") (pintype "unspecified"))
    )
    (net (code "34") (name "USB_N") (class "Default")
      (node (ref "U3") (pin "39") (pinfunction "USB_DM_39") (pintype "bidirectional"))
      (node (ref "U4") (pin "6") (pinfunction "D1_OUT_6") (pintype "unspecified"))
    )
    (net (code "35") (name "USB_P") (class "Default")
      (node (ref "U3") (pin "40") (pinfunction "USB_DP_40") (pintype "bidirectional"))
      (node (ref "U4") (pin "4") (pinfunction "D2_OUT_4") (pintype "unspecified"))
    )
    (net (code "36") (name "VBUS") (class "Default")
      (node (ref "C14") (pin "2") (pinfunction "2_2") (pintype "unspecified"))
      (node (ref "C15") (pin "2") (pinfunction "2_2") (pintype "unspecified"))
      (node (ref "D6") (pin "1") (pinfunction "A_1") (pintype "unspecified"))
      (node (ref "J1") (pin "A4") (pinfunction "VBUS_A4") (pintype "unspecified"))
      (node (ref "RT9013") (pin "1") (pinfunction "VIN_1") (pintype "unspecified"))
      (node (ref "U4") (pin "5") (pinfunction "VBUS_5") (pintype "unspecified"))
    )
    (net (code "37") (name "VCC_3V3") (class "Default")
      (node (ref "C19") (pin "1") (pinfunction "1_1") (pintype "unspecified"))
      (node (ref "C6") (pin "2") (pinfunction "2_2") (pintype "unspecified"))
      (node (ref "C7") (pin "2") (pinfunction "2_2") (pintype "unspecified"))
      (node (ref "D2") (pin "1") (pinfunction "A_1") (pintype "unspecified"))
      (node (ref "D3") (pin "A") (pinfunction "A_A") (pintype "unspecified"))
      (node (ref "D4") (pin "A") (pinfunction "A_A") (pintype "unspecified"))
      (node (ref "R1") (pin "2") (pinfunction "2_2") (pintype "unspecified"))
      (node (ref "R2") (pin "1") (pinfunction "1_1") (pintype "unspecified"))
      (node (ref "RT9013") (pin "3") (pinfunction "EN_3") (pintype "unspecified"))
      (node (ref "U1") (pin "8") (pinfunction "VOUT1_8") (pintype "unspecified"))
      (node (ref "U3") (pin "33") (pinfunction "VCC_33") (pintype "unspecified"))
      (node (ref "U3") (pin "34") (pinfunction "VCC_34") (pintype "unspecified"))
      (node (ref "V3.3") (pin "1") (pinfunction "1_1") (pintype "unspecified"))
      (node (ref "VCC-3.3V1") (pin "1") (pinfunction "1_1") (pintype "unspecified"))
    )
    (net (code "38") (name "VDD_3V3") (class "Default")
      (node (ref "C4") (pin "2") (pinfunction "2_2") (pintype "unspecified"))
      (node (ref "C5") (pin "2") (pinfunction "2_2") (pintype "unspecified"))
      (node (ref "D5") (pin "1") (pinfunction "A_1") (pintype "unspecified"))
      (node (ref "L1") (pin "1") (pinfunction "1_1") (pintype "unspecified"))
      (node (ref "T3") (pin "1") (pinfunction "1_1") (pintype "unspecified"))
      (node (ref "U1") (pin "7") (pinfunction "VOUT2_7") (pintype "unspecified"))
    )
    (net (code "39") (name "VDD_5V_IN") (class "Default")
      (node (ref "C1") (pin "2") (pinfunction "2_2") (pintype "unspecified"))
      (node (ref "C2") (pin "2") (pinfunction "2_2") (pintype "unspecified"))
      (node (ref "D6") (pin "2") (pinfunction "K_2") (pintype "unspecified"))
      (node (ref "P1") (pin "1") (pinfunction "1_1") (pintype "unspecified"))
      (node (ref "P2") (pin "1") (pinfunction "1_1") (pintype "unspecified"))
      (node (ref "R3") (pin "1") (pinfunction "1_1") (pintype "unspecified"))
      (node (ref "T1") (pin "1") (pinfunction "1_1") (pintype "unspecified"))
      (node (ref "U1") (pin "1") (pinfunction "VIN_1") (pintype "unspecified"))
    )
    (net (code "40") (name "V_BCKP") (class "Default")
      (node (ref "BT1") (pin "1") (pinfunction "1_1") (pintype "unspecified"))
      (node (ref "BT2") (pin "1") (pinfunction "1_1") (pintype "unspecified"))
      (node (ref "R10") (pin "2") (pinfunction "2_2") (pintype "unspecified"))
      (node (ref "U3") (pin "36") (pinfunction "V_BCKP_36") (pintype "unspecified"))
    )
    (net (code "41") (name "V_USB") (class "Default")
      (node (ref "C16") (pin "2") (pinfunction "2_2") (pintype "unspecified"))
      (node (ref "C17") (pin "2") (pinfunction "2_2") (pintype "unspecified"))
      (node (ref "R12") (pin "1") (pinfunction "1_1") (pintype "unspecified"))
      (node (ref "RT9013") (pin "5") (pinfunction "OUT_5") (pintype "unspecified"))
      (node (ref "U3") (pin "38") (pinfunction "V_USB_38") (pintype "unspecified"))
      (node (ref "USB-3.3V1") (pin "1") (pinfunction "1_1") (pintype "unspecified"))
    )
    (net (code "42") (name "unconnected-(J1-CC1-PadA5)") (class "Default")
      (node (ref "J1") (pin "A5") (pinfunction "CC1_A5") (pintype "unspecified"))
    )
    (net (code "43") (name "unconnected-(J1-CC2-PadA8)") (class "Default")
      (node (ref "J1") (pin "A8") (pinfunction "CC2_A8") (pintype "unspecified"))
    )
    (net (code "44") (name "unconnected-(J1-SHLD-PadS)") (class "Default")
      (node (ref "J1") (pin "S") (pinfunction "SHLD_S") (pintype "unspecified"))
    )
    (net (code "45") (name "unconnected-(U1-NC-Pad6)") (class "Default")
      (node (ref "U1") (pin "6") (pinfunction "NC_6") (pintype "unspecified"))
    )
    (net (code "46") (name "unconnected-(U2-NC-Pad3)") (class "Default")
      (node (ref "U2") (pin "3") (pinfunction "NC_3") (pintype "unspecified"))
    )
    (net (code "47") (name "unconnected-(U2-NC-Pad4)") (class "Default")
      (node (ref "U2") (pin "4") (pinfunction "NC_4") (pintype "unspecified"))
    )
    (net (code "48") (name "unconnected-(U2-NC-Pad8)") (class "Default")
      (node (ref "U2") (pin "8") (pinfunction "NC_8") (pintype "unspecified"))
    )
    (net (code "49") (name "unconnected-(U2-NC-Pad12)") (class "Default")
      (node (ref "U2") (pin "12") (pinfunction "NC_12") (pintype "unspecified"))
    )
    (net (code "50") (name "unconnected-(U2-VPP-Pad7)") (class "Default")
      (node (ref "U2") (pin "7") (pinfunction "VPP_7") (pintype "unspecified"))
    )
    (net (code "51") (name "unconnected-(U3A-ANT_DETECT-Pad4)") (class "Default")
      (node (ref "U3") (pin "4") (pinfunction "ANT_DETECT_4") (pintype "input"))
    )
    (net (code "52") (name "unconnected-(U3A-ANT_OFF-Pad5)") (class "Default")
      (node (ref "U3") (pin "5") (pinfunction "ANT_OFF_5") (pintype "output"))
    )
    (net (code "53") (name "unconnected-(U3A-ANT_SHORT_N-Pad6)") (class "Default")
      (node (ref "U3") (pin "6") (pinfunction "ANT_SHORT_N_6") (pintype "input"))
    )
    (net (code "54") (name "unconnected-(U3A-D_SEL-Pad47)") (class "Default")
      (node (ref "U3") (pin "47") (pinfunction "D_SEL_47") (pintype "input"))
    )
    (net (code "55") (name "unconnected-(U3A-RESERVED-Pad8)") (class "Default")
      (node (ref "U3") (pin "8") (pinfunction "RESERVED_8") (pintype "unspecified"))
    )
    (net (code "56") (name "unconnected-(U3A-RESERVED-Pad9)") (class "Default")
      (node (ref "U3") (pin "9") (pinfunction "RESERVED_9") (pintype "unspecified"))
    )
    (net (code "57") (name "unconnected-(U3A-RESERVED-Pad10)") (class "Default")
      (node (ref "U3") (pin "10") (pinfunction "RESERVED_10") (pintype "unspecified"))
    )
    (net (code "58") (name "unconnected-(U3A-RESERVED-Pad11)") (class "Default")
      (node (ref "U3") (pin "11") (pinfunction "RESERVED_11") (pintype "unspecified"))
    )
    (net (code "59") (name "unconnected-(U3A-RESERVED-Pad13)") (class "Default")
      (node (ref "U3") (pin "13") (pinfunction "RESERVED_13") (pintype "unspecified"))
    )
    (net (code "60") (name "unconnected-(U3A-RESERVED-Pad15)") (class "Default")
      (node (ref "U3") (pin "15") (pinfunction "RESERVED_15") (pintype "unspecified"))
    )
    (net (code "61") (name "unconnected-(U3A-RESERVED-Pad16)") (class "Default")
      (node (ref "U3") (pin "16") (pinfunction "RESERVED_16") (pintype "unspecified"))
    )
    (net (code "62") (name "unconnected-(U3A-RESERVED-Pad17)") (class "Default")
      (node (ref "U3") (pin "17") (pinfunction "RESERVED_17") (pintype "unspecified"))
    )
    (net (code "63") (name "unconnected-(U3A-RESERVED-Pad18)") (class "Default")
      (node (ref "U3") (pin "18") (pinfunction "RESERVED_18") (pintype "unspecified"))
    )
    (net (code "64") (name "unconnected-(U3A-RESERVED-Pad21)") (class "Default")
      (node (ref "U3") (pin "21") (pinfunction "RESERVED_21") (pintype "unspecified"))
    )
    (net (code "65") (name "unconnected-(U3A-RESERVED-Pad22)") (class "Default")
      (node (ref "U3") (pin "22") (pinfunction "RESERVED_22") (pintype "unspecified"))
    )
    (net (code "66") (name "unconnected-(U3A-RESERVED-Pad23)") (class "Default")
      (node (ref "U3") (pin "23") (pinfunction "RESERVED_23") (pintype "unspecified"))
    )
    (net (code "67") (name "unconnected-(U3A-RESERVED-Pad24)") (class "Default")
      (node (ref "U3") (pin "24") (pinfunction "RESERVED_24") (pintype "unspecified"))
    )
    (net (code "68") (name "unconnected-(U3A-RESERVED-Pad25)") (class "Default")
      (node (ref "U3") (pin "25") (pinfunction "RESERVED_25") (pintype "unspecified"))
    )
    (net (code "69") (name "unconnected-(U3A-RESERVED-Pad28)") (class "Default")
      (node (ref "U3") (pin "28") (pinfunction "RESERVED_28") (pintype "unspecified"))
    )
    (net (code "70") (name "unconnected-(U3A-RESERVED-Pad29)") (class "Default")
      (node (ref "U3") (pin "29") (pinfunction "RESERVED_29") (pintype "unspecified"))
    )
    (net (code "71") (name "unconnected-(U3A-RESERVED-Pad30)") (class "Default")
      (node (ref "U3") (pin "30") (pinfunction "RESERVED_30") (pintype "unspecified"))
    )
    (net (code "72") (name "unconnected-(U3A-RESERVED-Pad31)") (class "Default")
      (node (ref "U3") (pin "31") (pinfunction "RESERVED_31") (pintype "unspecified"))
    )
    (net (code "73") (name "unconnected-(U3A-RESERVED-Pad35)") (class "Default")
      (node (ref "U3") (pin "35") (pinfunction "RESERVED_35") (pintype "unspecified"))
    )
    (net (code "74") (name "unconnected-(U3A-SCL{slash}SPI_CLK-Pad45)") (class "Default")
      (node (ref "U3") (pin "45") (pinfunction "SCL/SPI_CLK_45") (pintype "bidirectional"))
    )
    (net (code "75") (name "unconnected-(U3A-SDA{slash}SPI_CS_N-Pad44)") (class "Default")
      (node (ref "U3") (pin "44") (pinfunction "SDA/SPI_CS_N_44") (pintype "bidirectional"))
    )
    (net (code "76") (name "unconnected-(U3A-TX_READY-Pad46)") (class "Default")
      (node (ref "U3") (pin "46") (pinfunction "TX_READY_46") (pintype "output"))
    )
    (net (code "77") (name "unconnected-(U3B-RESERVED-Pad52)") (class "Default")
      (node (ref "U3") (pin "52") (pinfunction "RESERVED_52") (pintype "unspecified"))
    )
  )
)
